# CAN.net
KiCad netlist of a schematic drawn in Altium Designer
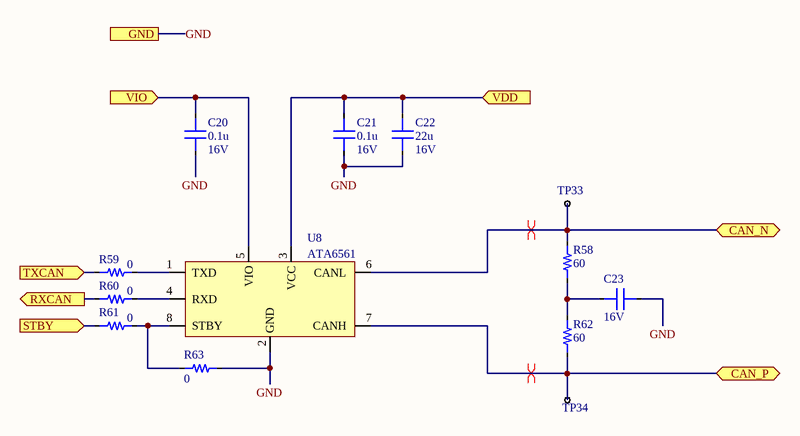
[diagram p0: CAN.SchDoc]

(export (version "E")
  (design (tool "Eeschema 10.0.6"))
  (components
    (comp (ref "C20")
      (value "0.1u")
      (footprint "0603_CAP")
      (fields (field (name "VOLTAGE") "16V") (field (name "Comment") "Capacitor"))
      (libsource (lib "Capacitors") (part "Capacitor"))
    )
    (comp (ref "C21")
      (value "0.1u")
      (footprint "0603_CAP")
      (fields (field (name "VOLTAGE") "16V") (field (name "Comment") "Capacitor"))
      (libsource (lib "Capacitors") (part "Capacitor"))
    )
    (comp (ref "C22")
      (value "22u")
      (footprint "0805_CAP")
      (fields (field (name "VOLTAGE") "16V") (field (name "Comment") "Capacitor"))
      (libsource (lib "Capacitors") (part "Capacitor"))
    )
    (comp (ref "C23")
      (value "Capacitor")
      (footprint "0603_CAP")
      (fields (field (name "VOLTAGE") "16V"))
      (libsource (lib "Capacitors") (part "Capacitor"))
    )
    (comp (ref "R58")
      (value "60")
      (footprint "0603_RES")
      (fields (field (name "Comment") "Resistor"))
      (libsource (lib "Resistors") (part "Resistor"))
    )
    (comp (ref "R59")
      (value "0")
      (footprint "0603_RES")
      (fields (field (name "Comment") "Resistor"))
      (libsource (lib "Resistors") (part "Resistor"))
    )
    (comp (ref "R60")
      (value "0")
      (footprint "0603_RES")
      (fields (field (name "Comment") "Resistor"))
      (libsource (lib "Resistors") (part "Resistor"))
    )
    (comp (ref "R61")
      (value "0")
      (footprint "0603_RES")
      (fields (field (name "Comment") "Resistor"))
      (libsource (lib "Resistors") (part "Resistor"))
    )
    (comp (ref "R62")
      (value "60")
      (footprint "0603_RES")
      (fields (field (name "Comment") "Resistor"))
      (libsource (lib "Resistors") (part "Resistor"))
    )
    (comp (ref "R63")
      (value "0")
      (footprint "0603_RES")
      (fields (field (name "Comment") "Resistor"))
      (libsource (lib "Resistors") (part "Resistor"))
    )
    (comp (ref "TP33")
      (value "1mm Testpoint")
      (footprint "1mm_testpoint")
      (description "1mm test point")
      (libsource (lib "Connectors") (part "1mm Testpoint"))
    )
    (comp (ref "TP34")
      (value "1mm Testpoint")
      (footprint "1mm_testpoint")
      (description "1mm test point")
      (libsource (lib "Connectors") (part "1mm Testpoint"))
    )
    (comp (ref "U8")
      (value "ATA6561")
      (footprint "SOIC-8")
      (description "1/1 Transceiver CANbus 8-SO")
      (libsource (lib "Interfaces") (part "ATA6561"))
    )
  )
  (nets
    (net (code "1") (name "/CAN_N") (class "Default")
      (node (ref "R58") (pin "2") (pinfunction "2_2") (pintype "passive"))
      (node (ref "TP33") (pin "1") (pintype "passive"))
      (node (ref "U8") (pin "6") (pinfunction "CANL_6") (pintype "passive"))
    )
    (net (code "2") (name "/CAN_P") (class "Default")
      (node (ref "R62") (pin "1") (pinfunction "1_1") (pintype "passive"))
      (node (ref "TP34") (pin "1") (pintype "passive"))
      (node (ref "U8") (pin "7") (pinfunction "CANH_7") (pintype "passive"))
    )
    (net (code "3") (name "/GND") (class "Default")
      (node (ref "C20") (pin "1") (pinfunction "1_1") (pintype "passive"))
      (node (ref "C21") (pin "1") (pinfunction "1_1") (pintype "passive"))
      (node (ref "C22") (pin "1") (pinfunction "1_1") (pintype "passive"))
      (node (ref "C23") (pin "2") (pinfunction "2_2") (pintype "passive"))
      (node (ref "R63") (pin "2") (pinfunction "2_2") (pintype "passive"))
      (node (ref "U8") (pin "2") (pinfunction "GND_2") (pintype "passive"))
    )
    (net (code "4") (name "/RXCAN") (class "Default")
      (node (ref "R60") (pin "1") (pinfunction "1_1") (pintype "passive"))
    )
    (net (code "5") (name "/STBY") (class "Default")
      (node (ref "R61") (pin "1") (pinfunction "1_1") (pintype "passive"))
    )
    (net (code "6") (name "/TXCAN") (class "Default")
      (node (ref "R59") (pin "1") (pinfunction "1_1") (pintype "passive"))
    )
    (net (code "7") (name "/VDD") (class "Default")
      (node (ref "C21") (pin "2") (pinfunction "2_2") (pintype "passive"))
      (node (ref "C22") (pin "2") (pinfunction "2_2") (pintype "passive"))
      (node (ref "U8") (pin "3") (pinfunction "VCC_3") (pintype "passive"))
    )
    (net (code "8") (name "/VIO") (class "Default")
      (node (ref "C20") (pin "2") (pinfunction "2_2") (pintype "passive"))
      (node (ref "U8") (pin "5") (pinfunction "VIO_5") (pintype "passive"))
    )
    (net (code "9") (name "Net-(C23-Pad1)") (class "Default")
      (node (ref "C23") (pin "1") (pinfunction "1_1") (pintype "passive"))
      (node (ref "R58") (pin "1") (pinfunction "1_1") (pintype "passive"))
      (node (ref "R62") (pin "2") (pinfunction "2_2") (pintype "passive"))
    )
    (net (code "10") (name "Net-(U8-RXD)") (class "Default")
      (node (ref "R60") (pin "2") (pinfunction "2_2") (pintype "passive"))
      (node (ref "U8") (pin "4") (pinfunction "RXD_4") (pintype "passive"))
    )
    (net (code "11") (name "Net-(U8-STBY)") (class "Default")
      (node (ref "R61") (pin "2") (pinfunction "2_2") (pintype "passive"))
      (node (ref "R63") (pin "1") (pinfunction "1_1") (pintype "passive"))
      (node (ref "U8") (pin "8") (pinfunction "STBY_8") (pintype "passive"))
    )
    (net (code "12") (name "Net-(U8-TXD)") (class "Default")
      (node (ref "R59") (pin "2") (pinfunction "2_2") (pintype "passive"))
      (node (ref "U8") (pin "1") (pinfunction "TXD_1") (pintype "passive"))
    )
  )
)
